# AmbaSat-02-STS21.net
KiCad netlist of a schematic drawn in EAGLE
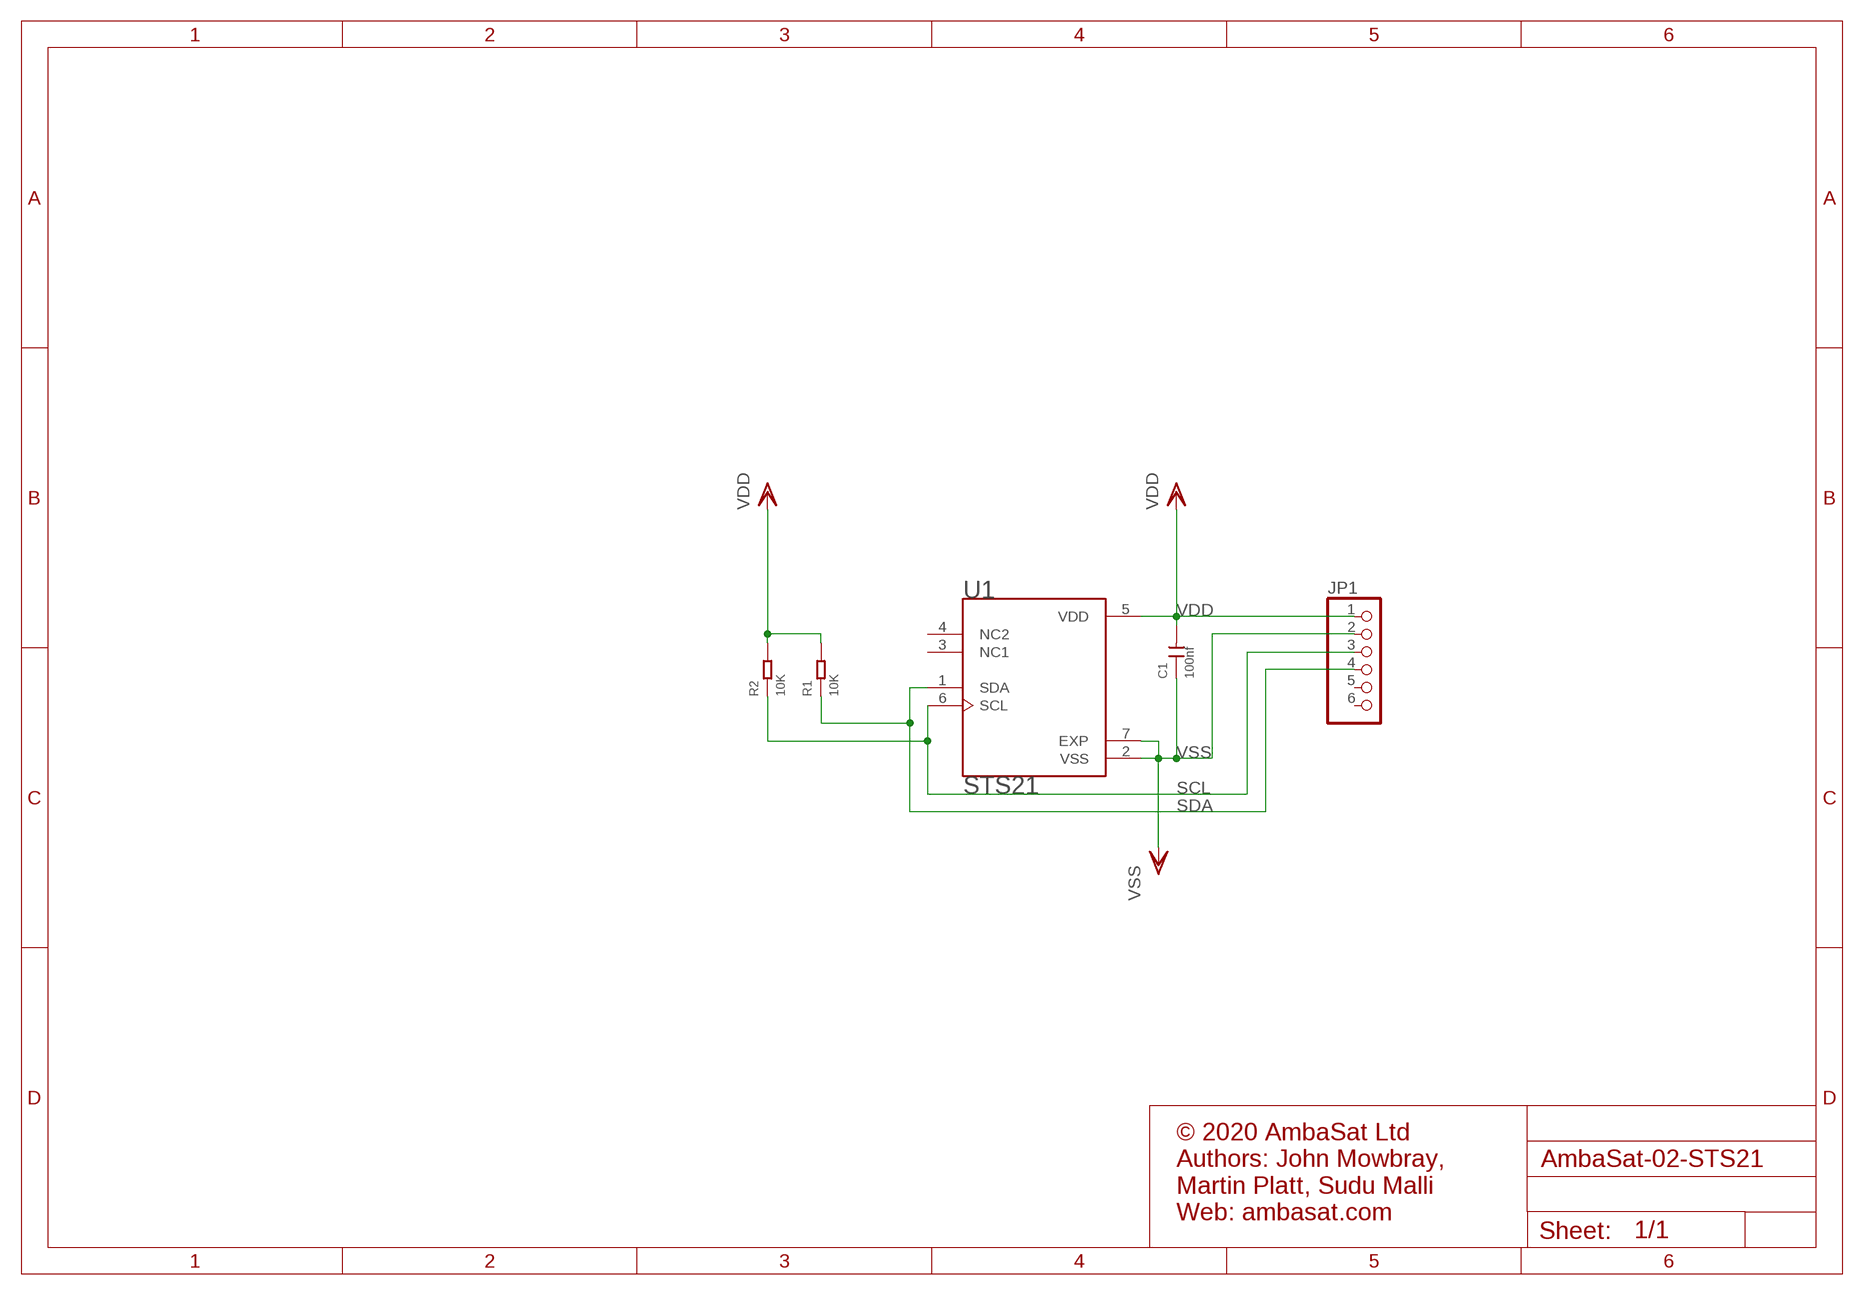
[diagram p0: schematic, sheet 1]

(export (version "E")
  (design (tool "Eeschema 10.0.6"))
  (components
    (comp (ref "C1")
      (value "100nf")
      (footprint "eagle-import:C0603")
      (fields (field (name "MPN") "CC0603KRX7R9BB104"))
      (libsource (lib "eagle-import") (part "CERAMIC-100NF-50V-10%-X7R(0603)"))
    )
    (comp (ref "JP1")
      (value "HEADER-1X6")
      (footprint "eagle-import:1X06_OVAL")
      (libsource (lib "eagle-import") (part "HEADER-1X6"))
    )
    (comp (ref "R1")
      (value "10K")
      (footprint "eagle-import:R0603")
      (fields (field (name "MPN") "RC0603FR-0710KL"))
      (libsource (lib "eagle-import") (part "SMD-RES-10K-1%-1/10W(0603)"))
    )
    (comp (ref "R2")
      (value "10K")
      (footprint "eagle-import:R0603")
      (fields (field (name "MPN") "RC0603FR-0710KL"))
      (libsource (lib "eagle-import") (part "SMD-RES-10K-1%-1/10W(0603)"))
    )
    (comp (ref "U1")
      (value "STS21")
      (footprint "eagle-import:XDCR_SGP30-2.5K")
      (libsource (lib "eagle-import") (part "STS21"))
    )
  )
  (nets
    (net (code "1") (name "/SCL") (class "Default")
      (node (ref "JP1") (pin "3") (pinfunction "3_3") (pintype "passive"))
      (node (ref "R2") (pin "1") (pinfunction "1_1") (pintype "passive"))
      (node (ref "U1") (pin "6") (pinfunction "SCL_6") (pintype "bidirectional"))
    )
    (net (code "2") (name "/SDA") (class "Default")
      (node (ref "JP1") (pin "4") (pinfunction "4_4") (pintype "passive"))
      (node (ref "R1") (pin "1") (pinfunction "1_1") (pintype "passive"))
      (node (ref "U1") (pin "1") (pinfunction "SDA_1") (pintype "bidirectional"))
    )
    (net (code "3") (name "VDD") (class "Default")
      (node (ref "C1") (pin "2") (pinfunction "2_2") (pintype "passive"))
      (node (ref "JP1") (pin "1") (pinfunction "1_1") (pintype "passive"))
      (node (ref "R1") (pin "2") (pinfunction "2_2") (pintype "passive"))
      (node (ref "R2") (pin "2") (pinfunction "2_2") (pintype "passive"))
      (node (ref "U1") (pin "5") (pinfunction "VDD_5") (pintype "power_in"))
    )
    (net (code "4") (name "VSS") (class "Default")
      (node (ref "C1") (pin "1") (pinfunction "1_1") (pintype "passive"))
      (node (ref "JP1") (pin "2") (pinfunction "2_2") (pintype "passive"))
      (node (ref "U1") (pin "2") (pinfunction "VSS_2") (pintype "passive"))
      (node (ref "U1") (pin "7") (pinfunction "EXP_7") (pintype "passive"))
    )
    (net (code "5") (name "unconnected-(JP1-Pad5)") (class "Default")
      (node (ref "JP1") (pin "5") (pinfunction "5_5") (pintype "passive"))
    )
    (net (code "6") (name "unconnected-(JP1-Pad6)") (class "Default")
      (node (ref "JP1") (pin "6") (pinfunction "6_6") (pintype "passive"))
    )
    (net (code "7") (name "unconnected-(U1-NC1-Pad3)") (class "Default")
      (node (ref "U1") (pin "3") (pinfunction "NC1_3") (pintype "input"))
    )
    (net (code "8") (name "unconnected-(U1-NC2-Pad4)") (class "Default")
      (node (ref "U1") (pin "4") (pinfunction "NC2_4") (pintype "input"))
    )
  )
)
